# controller.net
KiCad netlist of a schematic drawn in Altium Designer
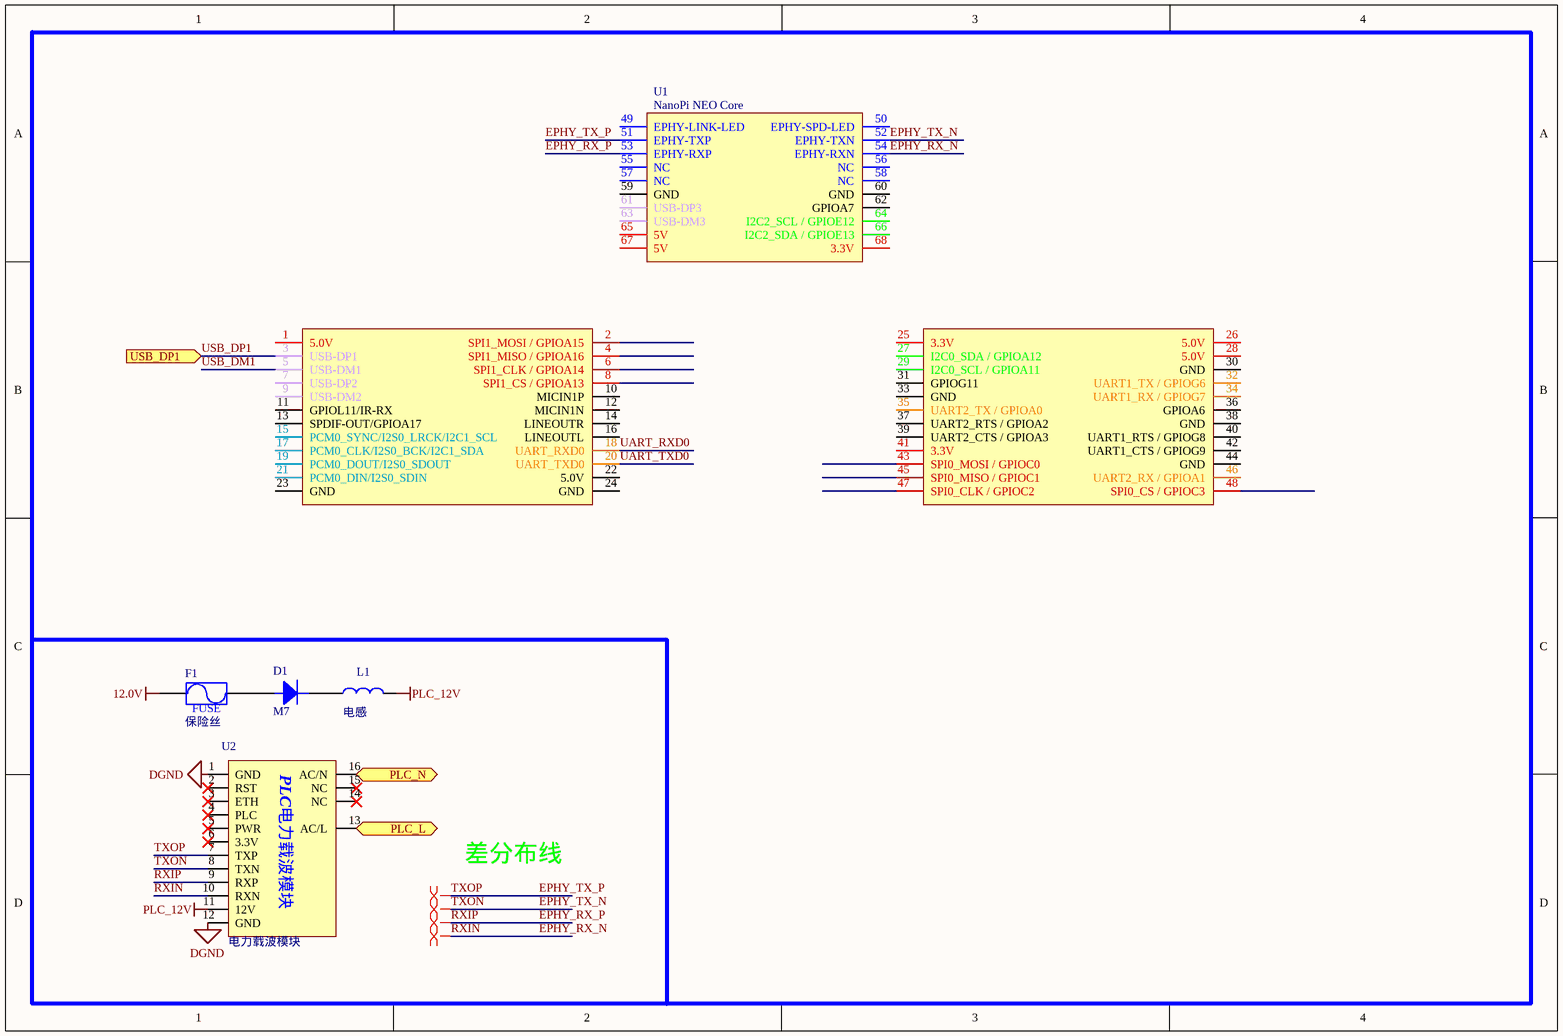
[diagram p0: controller.SchDoc]

(export (version "E")
  (design (tool "Eeschema 10.0.6"))
  (components
    (comp (ref "D1")
      (value "M7")
      (footprint "SMA/DO-214AC")
      (description "二极管")
      (libsource (lib "集大电协1.5") (part "Diode"))
    )
    (comp (ref "F1") (value "保险丝") (footprint "FUSE-1206") (libsource (lib "集大电协1.2") (part "Fuse")))
    (comp (ref "L1") (value "电感") (footprint "1206L") (libsource (lib "集大电协1.5") (part "L")))
    (comp (ref "U1")
      (value "NanoPi NEO Core")
      (footprint "NanoPi NEO Core")
      (libsource (lib "集大电协1.5") (part "NanoPi NEO Core"))
    )
    (comp (ref "U2")
      (value "电力载波模块")
      (footprint "电力载波模块6410")
      (libsource (lib "集大电协1.2") (part "电力载波模块6410"))
    )
  )
  (nets
    (net (code "1") (name "/EPHY_RX_N") (class "Default")
      (node (ref "U1") (pin "54") (pinfunction "EPHY-RXN_54") (pintype "passive"))
      (node (ref "U2") (pin "10") (pinfunction "RXN_10") (pintype "passive"))
    )
    (net (code "2") (name "/EPHY_RX_P") (class "Default")
      (node (ref "U1") (pin "53") (pinfunction "EPHY-RXP_53") (pintype "passive"))
      (node (ref "U2") (pin "9") (pinfunction "RXP_9") (pintype "passive"))
    )
    (net (code "3") (name "/EPHY_TX_N") (class "Default")
      (node (ref "U1") (pin "52") (pinfunction "EPHY-TXN_52") (pintype "passive"))
      (node (ref "U2") (pin "8") (pinfunction "TXN_8") (pintype "passive"))
    )
    (net (code "4") (name "/EPHY_TX_P") (class "Default")
      (node (ref "U1") (pin "51") (pinfunction "EPHY-TXP_51") (pintype "passive"))
      (node (ref "U2") (pin "7") (pinfunction "TXP_7") (pintype "passive"))
    )
    (net (code "5") (name "/PLC_L") (class "Default")
      (node (ref "U2") (pin "13") (pinfunction "AC/L_13") (pintype "passive"))
    )
    (net (code "6") (name "/PLC_N") (class "Default")
      (node (ref "U2") (pin "16") (pinfunction "AC/N_16") (pintype "passive"))
    )
    (net (code "7") (name "/UART_RXD0") (class "Default")
      (node (ref "U1") (pin "18") (pinfunction "UART_RXD0_18") (pintype "passive"))
    )
    (net (code "8") (name "/UART_TXD0") (class "Default")
      (node (ref "U1") (pin "20") (pinfunction "UART_TXD0_20") (pintype "passive"))
    )
    (net (code "9") (name "/USB_DM1") (class "Default")
      (node (ref "U1") (pin "5") (pinfunction "USB-DM1_5") (pintype "passive"))
    )
    (net (code "10") (name "/USB_DP1") (class "Default")
      (node (ref "U1") (pin "3") (pinfunction "USB-DP1_3") (pintype "passive"))
    )
    (net (code "11") (name "12.0V") (class "Default")
      (node (ref "F1") (pin "1") (pinfunction "1_1") (pintype "passive"))
    )
    (net (code "12") (name "DGND") (class "Default")
      (node (ref "U2") (pin "1") (pinfunction "GND_1") (pintype "passive"))
      (node (ref "U2") (pin "12") (pinfunction "GND_12") (pintype "passive"))
    )
    (net (code "13") (name "Net-(D1-Pad1)") (class "Default")
      (node (ref "D1") (pin "1") (pintype "passive"))
      (node (ref "F1") (pin "2") (pinfunction "2_2") (pintype "passive"))
    )
    (net (code "14") (name "Net-(D1-Pad2)") (class "Default")
      (node (ref "D1") (pin "2") (pinfunction "2_2") (pintype "passive"))
      (node (ref "L1") (pin "1") (pinfunction "1_1") (pintype "passive"))
    )
    (net (code "15") (name "PLC_12V") (class "Default")
      (node (ref "L1") (pin "2") (pinfunction "2_2") (pintype "passive"))
      (node (ref "U2") (pin "11") (pinfunction "12V_11") (pintype "passive"))
    )
    (net (code "16") (name "unconnected-(U1-3.3V-Pad25)") (class "Default")
      (node (ref "U1") (pin "25") (pinfunction "3.3V_25") (pintype "passive"))
    )
    (net (code "17") (name "unconnected-(U1-3.3V-Pad41)") (class "Default")
      (node (ref "U1") (pin "41") (pinfunction "3.3V_41") (pintype "passive"))
    )
    (net (code "18") (name "unconnected-(U1-3.3V-Pad68)") (class "Default")
      (node (ref "U1") (pin "68") (pinfunction "3.3V_68") (pintype "passive"))
    )
    (net (code "19") (name "unconnected-(U1-5.0V-Pad1)") (class "Default")
      (node (ref "U1") (pin "1") (pinfunction "5.0V_1") (pintype "passive"))
    )
    (net (code "20") (name "unconnected-(U1-5.0V-Pad22)") (class "Default")
      (node (ref "U1") (pin "22") (pinfunction "5.0V_22") (pintype "passive"))
    )
    (net (code "21") (name "unconnected-(U1-5.0V-Pad26)") (class "Default")
      (node (ref "U1") (pin "26") (pinfunction "5.0V_26") (pintype "passive"))
    )
    (net (code "22") (name "unconnected-(U1-5.0V-Pad28)") (class "Default")
      (node (ref "U1") (pin "28") (pinfunction "5.0V_28") (pintype "passive"))
    )
    (net (code "23") (name "unconnected-(U1-5V-Pad65)") (class "Default")
      (node (ref "U1") (pin "65") (pinfunction "5V_65") (pintype "passive"))
    )
    (net (code "24") (name "unconnected-(U1-5V-Pad67)") (class "Default")
      (node (ref "U1") (pin "67") (pinfunction "5V_67") (pintype "passive"))
    )
    (net (code "25") (name "unconnected-(U1-EPHY-LINK-LED-Pad49)") (class "Default")
      (node (ref "U1") (pin "49") (pinfunction "EPHY-LINK-LED_49") (pintype "passive"))
    )
    (net (code "26") (name "unconnected-(U1-EPHY-SPD-LED-Pad50)") (class "Default")
      (node (ref "U1") (pin "50") (pinfunction "EPHY-SPD-LED_50") (pintype "passive"))
    )
    (net (code "27") (name "unconnected-(U1-GND-Pad23)") (class "Default")
      (node (ref "U1") (pin "23") (pinfunction "GND_23") (pintype "passive"))
    )
    (net (code "28") (name "unconnected-(U1-GND-Pad24)") (class "Default")
      (node (ref "U1") (pin "24") (pinfunction "GND_24") (pintype "passive"))
    )
    (net (code "29") (name "unconnected-(U1-GND-Pad30)") (class "Default")
      (node (ref "U1") (pin "30") (pinfunction "GND_30") (pintype "passive"))
    )
    (net (code "30") (name "unconnected-(U1-GND-Pad33)") (class "Default")
      (node (ref "U1") (pin "33") (pinfunction "GND_33") (pintype "passive"))
    )
    (net (code "31") (name "unconnected-(U1-GND-Pad38)") (class "Default")
      (node (ref "U1") (pin "38") (pinfunction "GND_38") (pintype "passive"))
    )
    (net (code "32") (name "unconnected-(U1-GND-Pad44)") (class "Default")
      (node (ref "U1") (pin "44") (pinfunction "GND_44") (pintype "passive"))
    )
    (net (code "33") (name "unconnected-(U1-GND-Pad59)") (class "Default")
      (node (ref "U1") (pin "59") (pinfunction "GND_59") (pintype "passive"))
    )
    (net (code "34") (name "unconnected-(U1-GND-Pad60)") (class "Default")
      (node (ref "U1") (pin "60") (pinfunction "GND_60") (pintype "passive"))
    )
    (net (code "35") (name "unconnected-(U1-GPIOA6-Pad36)") (class "Default")
      (node (ref "U1") (pin "36") (pinfunction "GPIOA6_36") (pintype "passive"))
    )
    (net (code "36") (name "unconnected-(U1-GPIOA7-Pad62)") (class "Default")
      (node (ref "U1") (pin "62") (pinfunction "GPIOA7_62") (pintype "passive"))
    )
    (net (code "37") (name "unconnected-(U1-GPIOG11-Pad31)") (class "Default")
      (node (ref "U1") (pin "31") (pinfunction "GPIOG11_31") (pintype "passive"))
    )
    (net (code "38") (name "unconnected-(U1-GPIOL11{slash}IR-RX-Pad11)") (class "Default")
      (node (ref "U1") (pin "11") (pinfunction "GPIOL11/IR-RX_11") (pintype "passive"))
    )
    (net (code "39") (name "unconnected-(U1-I2C0_SCL_{slash}_GPIOA11-Pad29)") (class "Default")
      (node (ref "U1") (pin "29") (pinfunction "I2C0_SCL_/_GPIOA11_29") (pintype "passive"))
    )
    (net (code "40") (name "unconnected-(U1-I2C0_SDA_{slash}_GPIOA12-Pad27)") (class "Default")
      (node (ref "U1") (pin "27") (pinfunction "I2C0_SDA_/_GPIOA12_27") (pintype "passive"))
    )
    (net (code "41") (name "unconnected-(U1-I2C2_SCL_{slash}_GPIOE12-Pad64)") (class "Default")
      (node (ref "U1") (pin "64") (pinfunction "I2C2_SCL_/_GPIOE12_64") (pintype "passive"))
    )
    (net (code "42") (name "unconnected-(U1-I2C2_SDA_{slash}_GPIOE13-Pad66)") (class "Default")
      (node (ref "U1") (pin "66") (pinfunction "I2C2_SDA_/_GPIOE13_66") (pintype "passive"))
    )
    (net (code "43") (name "unconnected-(U1-LINEOUTL-Pad16)") (class "Default")
      (node (ref "U1") (pin "16") (pinfunction "LINEOUTL_16") (pintype "passive"))
    )
    (net (code "44") (name "unconnected-(U1-LINEOUTR-Pad14)") (class "Default")
      (node (ref "U1") (pin "14") (pinfunction "LINEOUTR_14") (pintype "passive"))
    )
    (net (code "45") (name "unconnected-(U1-MICIN1N-Pad12)") (class "Default")
      (node (ref "U1") (pin "12") (pinfunction "MICIN1N_12") (pintype "passive"))
    )
    (net (code "46") (name "unconnected-(U1-MICIN1P-Pad10)") (class "Default")
      (node (ref "U1") (pin "10") (pinfunction "MICIN1P_10") (pintype "passive"))
    )
    (net (code "47") (name "unconnected-(U1-NC-Pad55)") (class "Default")
      (node (ref "U1") (pin "55") (pinfunction "NC_55") (pintype "passive"))
    )
    (net (code "48") (name "unconnected-(U1-NC-Pad56)") (class "Default")
      (node (ref "U1") (pin "56") (pinfunction "NC_56") (pintype "passive"))
    )
    (net (code "49") (name "unconnected-(U1-NC-Pad57)") (class "Default")
      (node (ref "U1") (pin "57") (pinfunction "NC_57") (pintype "passive"))
    )
    (net (code "50") (name "unconnected-(U1-NC-Pad58)") (class "Default")
      (node (ref "U1") (pin "58") (pinfunction "NC_58") (pintype "passive"))
    )
    (net (code "51") (name "unconnected-(U1-PCM0_CLK{slash}I2S0_BCK{slash}I2C1_SDA-Pad17)") (class "Default")
      (node (ref "U1") (pin "17") (pinfunction "PCM0_CLK/I2S0_BCK/I2C1_SDA_17") (pintype "passive"))
    )
    (net (code "52") (name "unconnected-(U1-PCM0_DIN{slash}I2S0_SDIN-Pad21)") (class "Default")
      (node (ref "U1") (pin "21") (pinfunction "PCM0_DIN/I2S0_SDIN_21") (pintype "passive"))
    )
    (net (code "53") (name "unconnected-(U1-PCM0_DOUT{slash}I2S0_SDOUT-Pad19)") (class "Default")
      (node (ref "U1") (pin "19") (pinfunction "PCM0_DOUT/I2S0_SDOUT_19") (pintype "passive"))
    )
    (net (code "54") (name "unconnected-(U1-PCM0_SYNC{slash}I2S0_LRCK{slash}I2C1_SCL-Pad15)") (class "Default")
      (node (ref "U1") (pin "15") (pinfunction "PCM0_SYNC/I2S0_LRCK/I2C1_SCL_15") (pintype "passive"))
    )
    (net (code "55") (name "unconnected-(U1-SPDIF-OUT{slash}GPIOA17-Pad13)") (class "Default")
      (node (ref "U1") (pin "13") (pinfunction "SPDIF-OUT/GPIOA17_13") (pintype "passive"))
    )
    (net (code "56") (name "unconnected-(U1-SPI0_CLK_{slash}_GPIOC2-Pad47)") (class "Default")
      (node (ref "U1") (pin "47") (pinfunction "SPI0_CLK_/_GPIOC2_47") (pintype "passive"))
    )
    (net (code "57") (name "unconnected-(U1-SPI0_CS_{slash}_GPIOC3-Pad48)") (class "Default")
      (node (ref "U1") (pin "48") (pinfunction "SPI0_CS_/_GPIOC3_48") (pintype "passive"))
    )
    (net (code "58") (name "unconnected-(U1-SPI0_MISO_{slash}_GPIOC1-Pad45)") (class "Default")
      (node (ref "U1") (pin "45") (pinfunction "SPI0_MISO_/_GPIOC1_45") (pintype "passive"))
    )
    (net (code "59") (name "unconnected-(U1-SPI0_MOSI_{slash}_GPIOC0-Pad43)") (class "Default")
      (node (ref "U1") (pin "43") (pinfunction "SPI0_MOSI_/_GPIOC0_43") (pintype "passive"))
    )
    (net (code "60") (name "unconnected-(U1-SPI1_CLK_{slash}_GPIOA14-Pad6)") (class "Default")
      (node (ref "U1") (pin "6") (pinfunction "SPI1_CLK_/_GPIOA14_6") (pintype "passive"))
    )
    (net (code "61") (name "unconnected-(U1-SPI1_CS_{slash}_GPIOA13-Pad8)") (class "Default")
      (node (ref "U1") (pin "8") (pinfunction "SPI1_CS_/_GPIOA13_8") (pintype "passive"))
    )
    (net (code "62") (name "unconnected-(U1-SPI1_MISO_{slash}_GPIOA16-Pad4)") (class "Default")
      (node (ref "U1") (pin "4") (pinfunction "SPI1_MISO_/_GPIOA16_4") (pintype "passive"))
    )
    (net (code "63") (name "unconnected-(U1-SPI1_MOSI_{slash}_GPIOA15-Pad2)") (class "Default")
      (node (ref "U1") (pin "2") (pinfunction "SPI1_MOSI_/_GPIOA15_2") (pintype "passive"))
    )
    (net (code "64") (name "unconnected-(U1-UART1_CTS_{slash}_GPIOG9-Pad42)") (class "Default")
      (node (ref "U1") (pin "42") (pinfunction "UART1_CTS_/_GPIOG9_42") (pintype "passive"))
    )
    (net (code "65") (name "unconnected-(U1-UART1_RTS_{slash}_GPIOG8-Pad40)") (class "Default")
      (node (ref "U1") (pin "40") (pinfunction "UART1_RTS_/_GPIOG8_40") (pintype "passive"))
    )
    (net (code "66") (name "unconnected-(U1-UART1_RX_{slash}_GPIOG7-Pad34)") (class "Default")
      (node (ref "U1") (pin "34") (pinfunction "UART1_RX_/_GPIOG7_34") (pintype "passive"))
    )
    (net (code "67") (name "unconnected-(U1-UART1_TX_{slash}_GPIOG6-Pad32)") (class "Default")
      (node (ref "U1") (pin "32") (pinfunction "UART1_TX_/_GPIOG6_32") (pintype "passive"))
    )
    (net (code "68") (name "unconnected-(U1-UART2_CTS_{slash}_GPIOA3-Pad39)") (class "Default")
      (node (ref "U1") (pin "39") (pinfunction "UART2_CTS_/_GPIOA3_39") (pintype "passive"))
    )
    (net (code "69") (name "unconnected-(U1-UART2_RTS_{slash}_GPIOA2-Pad37)") (class "Default")
      (node (ref "U1") (pin "37") (pinfunction "UART2_RTS_/_GPIOA2_37") (pintype "passive"))
    )
    (net (code "70") (name "unconnected-(U1-UART2_RX_{slash}_GPIOA1-Pad46)") (class "Default")
      (node (ref "U1") (pin "46") (pinfunction "UART2_RX_/_GPIOA1_46") (pintype "passive"))
    )
    (net (code "71") (name "unconnected-(U1-UART2_TX_{slash}_GPIOA0-Pad35)") (class "Default")
      (node (ref "U1") (pin "35") (pinfunction "UART2_TX_/_GPIOA0_35") (pintype "passive"))
    )
    (net (code "72") (name "unconnected-(U1-USB-DM2-Pad9)") (class "Default")
      (node (ref "U1") (pin "9") (pinfunction "USB-DM2_9") (pintype "passive"))
    )
    (net (code "73") (name "unconnected-(U1-USB-DM3-Pad63)") (class "Default")
      (node (ref "U1") (pin "63") (pinfunction "USB-DM3_63") (pintype "passive"))
    )
    (net (code "74") (name "unconnected-(U1-USB-DP2-Pad7)") (class "Default")
      (node (ref "U1") (pin "7") (pinfunction "USB-DP2_7") (pintype "passive"))
    )
    (net (code "75") (name "unconnected-(U1-USB-DP3-Pad61)") (class "Default")
      (node (ref "U1") (pin "61") (pinfunction "USB-DP3_61") (pintype "passive"))
    )
    (net (code "76") (name "unconnected-(U2-3.3V-Pad6)") (class "Default")
      (node (ref "U2") (pin "6") (pinfunction "3.3V_6") (pintype "passive+no_connect"))
    )
    (net (code "77") (name "unconnected-(U2-ETH-Pad3)") (class "Default")
      (node (ref "U2") (pin "3") (pinfunction "ETH_3") (pintype "passive+no_connect"))
    )
    (net (code "78") (name "unconnected-(U2-NC-Pad14)") (class "Default")
      (node (ref "U2") (pin "14") (pinfunction "NC_14") (pintype "passive+no_connect"))
    )
    (net (code "79") (name "unconnected-(U2-NC-Pad15)") (class "Default")
      (node (ref "U2") (pin "15") (pinfunction "NC_15") (pintype "passive+no_connect"))
    )
    (net (code "80") (name "unconnected-(U2-PLC-Pad4)") (class "Default")
      (node (ref "U2") (pin "4") (pinfunction "PLC_4") (pintype "passive+no_connect"))
    )
    (net (code "81") (name "unconnected-(U2-PWR-Pad5)") (class "Default")
      (node (ref "U2") (pin "5") (pinfunction "PWR_5") (pintype "passive+no_connect"))
    )
    (net (code "82") (name "unconnected-(U2-RST-Pad2)") (class "Default")
      (node (ref "U2") (pin "2") (pinfunction "RST_2") (pintype "passive+no_connect"))
    )
  )
)
